# nadajnik.net
KiCad netlist of a schematic drawn in EAGLE
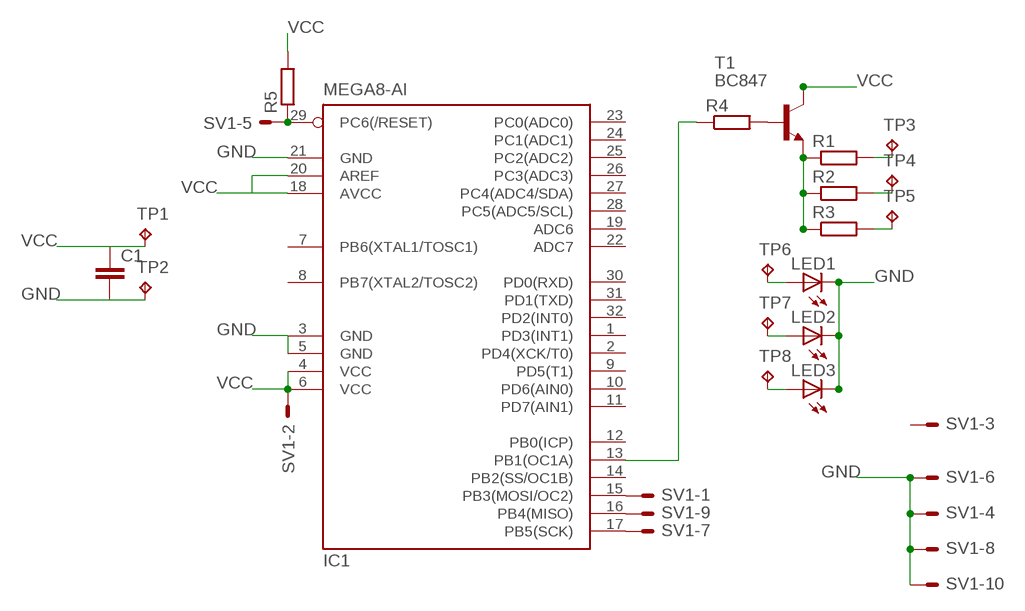
[diagram p0: schematic, sheet 1]

(export (version "E")
  (design (tool "Eeschema 10.0.6"))
  (components
    (comp (ref "C1")
      (value "C-EUC1206")
      (footprint "eagle-import:C1206")
      (libsource (lib "eagle-import") (part "C-EUC1206"))
    )
    (comp (ref "IC1")
      (value "MEGA8-AI")
      (footprint "eagle-import:TQFP32-08")
      (fields (field (name "MPN") "ATMEGA8-16AU"))
      (libsource (lib "eagle-import") (part "MEGA8-AI"))
    )
    (comp (ref "LED1")
      (value "LEDSFH480")
      (footprint "eagle-import:SFH480")
      (libsource (lib "eagle-import") (part "LEDSFH480"))
    )
    (comp (ref "LED2")
      (value "LEDSFH480")
      (footprint "eagle-import:SFH480")
      (libsource (lib "eagle-import") (part "LEDSFH480"))
    )
    (comp (ref "LED3")
      (value "LEDSFH480")
      (footprint "eagle-import:SFH480")
      (libsource (lib "eagle-import") (part "LEDSFH480"))
    )
    (comp (ref "R1")
      (value "R-EU_R1206")
      (footprint "eagle-import:R1206")
      (libsource (lib "eagle-import") (part "resistor_R-EU_R1206"))
    )
    (comp (ref "R2")
      (value "R-EU_R1206")
      (footprint "eagle-import:R1206")
      (libsource (lib "eagle-import") (part "resistor_R-EU_R1206"))
    )
    (comp (ref "R3")
      (value "R-EU_R1206")
      (footprint "eagle-import:R1206")
      (libsource (lib "eagle-import") (part "resistor_R-EU_R1206"))
    )
    (comp (ref "R4")
      (value "R-EU_R1206")
      (footprint "eagle-import:R1206")
      (libsource (lib "eagle-import") (part "R-EU_R1206"))
    )
    (comp (ref "R5")
      (value "R-EU_R1206")
      (footprint "eagle-import:R1206")
      (libsource (lib "eagle-import") (part "R-EU_R1206"))
    )
    (comp (ref "SV1")
      (value "ML10E")
      (footprint "eagle-import:ML10")
      (libsource (lib "eagle-import") (part "ML10E"))
    )
    (comp (ref "T1")
      (value "BC847")
      (footprint "eagle-import:SOT23")
      (libsource (lib "eagle-import") (part "BC847"))
    )
    (comp (ref "TP1")
      (value "TPPAD1-13Y")
      (footprint "eagle-import:P1-13Y")
      (libsource (lib "eagle-import") (part "TPPAD1-13Y"))
    )
    (comp (ref "TP2")
      (value "TPPAD1-13Y")
      (footprint "eagle-import:P1-13Y")
      (libsource (lib "eagle-import") (part "TPPAD1-13Y"))
    )
    (comp (ref "TP3")
      (value "TPPAD1-13Y")
      (footprint "eagle-import:P1-13Y")
      (libsource (lib "eagle-import") (part "TPPAD1-13Y"))
    )
    (comp (ref "TP4")
      (value "TPPAD1-13Y")
      (footprint "eagle-import:P1-13Y")
      (libsource (lib "eagle-import") (part "TPPAD1-13Y"))
    )
    (comp (ref "TP5")
      (value "TPPAD1-13Y")
      (footprint "eagle-import:P1-13Y")
      (libsource (lib "eagle-import") (part "TPPAD1-13Y"))
    )
    (comp (ref "TP6")
      (value "TPPAD1-13Y")
      (footprint "eagle-import:P1-13Y")
      (libsource (lib "eagle-import") (part "TPPAD1-13Y"))
    )
    (comp (ref "TP7")
      (value "TPPAD1-13Y")
      (footprint "eagle-import:P1-13Y")
      (libsource (lib "eagle-import") (part "TPPAD1-13Y"))
    )
    (comp (ref "TP8")
      (value "TPPAD1-13Y")
      (footprint "eagle-import:P1-13Y")
      (libsource (lib "eagle-import") (part "TPPAD1-13Y"))
    )
  )
  (nets
    (net (code "1") (name "/GND") (class "Default")
      (node (ref "C1") (pin "2") (pinfunction "2_2") (pintype "passive"))
      (node (ref "IC1") (pin "21") (pinfunction "GND_21") (pintype "power_in"))
      (node (ref "IC1") (pin "3") (pinfunction "GND_3") (pintype "power_in"))
      (node (ref "IC1") (pin "5") (pinfunction "GND_5") (pintype "power_in"))
      (node (ref "LED1") (pin "K") (pinfunction "C_K") (pintype "passive"))
      (node (ref "LED2") (pin "K") (pinfunction "C_K") (pintype "passive"))
      (node (ref "LED3") (pin "K") (pinfunction "C_K") (pintype "passive"))
      (node (ref "SV1") (pin "10") (pinfunction "S_10") (pintype "passive"))
      (node (ref "SV1") (pin "4") (pinfunction "S_4") (pintype "passive"))
      (node (ref "SV1") (pin "6") (pinfunction "S_6") (pintype "passive"))
      (node (ref "SV1") (pin "8") (pinfunction "S_8") (pintype "passive"))
      (node (ref "TP2") (pin "TP") (pinfunction "TP_TP") (pintype "input"))
    )
    (net (code "2") (name "/VCC") (class "Default")
      (node (ref "C1") (pin "1") (pinfunction "1_1") (pintype "passive"))
      (node (ref "IC1") (pin "18") (pinfunction "AVCC_18") (pintype "power_in"))
      (node (ref "IC1") (pin "20") (pinfunction "AREF_20") (pintype "passive"))
      (node (ref "IC1") (pin "4") (pinfunction "VCC_4") (pintype "power_in"))
      (node (ref "IC1") (pin "6") (pinfunction "VCC_6") (pintype "power_in"))
      (node (ref "R5") (pin "2") (pinfunction "2_2") (pintype "passive"))
      (node (ref "SV1") (pin "2") (pinfunction "S_2") (pintype "passive"))
      (node (ref "T1") (pin "3") (pinfunction "C_3") (pintype "passive"))
      (node (ref "TP1") (pin "TP") (pinfunction "TP_TP") (pintype "input"))
    )
    (net (code "3") (name "Net-(IC1-PB1(OC1A))") (class "Default")
      (node (ref "IC1") (pin "13") (pinfunction "PB1(OC1A)_13") (pintype "bidirectional"))
      (node (ref "R4") (pin "1") (pinfunction "1_1") (pintype "passive"))
    )
    (net (code "4") (name "Net-(IC1-PB3(MOSI{slash}OC2))") (class "Default")
      (node (ref "IC1") (pin "15") (pinfunction "PB3(MOSI/OC2)_15") (pintype "bidirectional"))
      (node (ref "SV1") (pin "1") (pinfunction "S_1") (pintype "passive"))
    )
    (net (code "5") (name "Net-(IC1-PB4(MISO))") (class "Default")
      (node (ref "IC1") (pin "16") (pinfunction "PB4(MISO)_16") (pintype "bidirectional"))
      (node (ref "SV1") (pin "9") (pinfunction "S_9") (pintype "passive"))
    )
    (net (code "6") (name "Net-(IC1-PB5(SCK))") (class "Default")
      (node (ref "IC1") (pin "17") (pinfunction "PB5(SCK)_17") (pintype "bidirectional"))
      (node (ref "SV1") (pin "7") (pinfunction "S_7") (pintype "passive"))
    )
    (net (code "7") (name "Net-(IC1-PC6({slash}RESET))") (class "Default")
      (node (ref "IC1") (pin "29") (pinfunction "PC6(/RESET)_29") (pintype "bidirectional"))
      (node (ref "R5") (pin "1") (pinfunction "1_1") (pintype "passive"))
      (node (ref "SV1") (pin "5") (pinfunction "S_5") (pintype "passive"))
    )
    (net (code "8") (name "Net-(LED1-PadA)") (class "Default")
      (node (ref "LED1") (pin "A") (pinfunction "A_A") (pintype "passive"))
      (node (ref "TP6") (pin "TP") (pinfunction "TP_TP") (pintype "input"))
    )
    (net (code "9") (name "Net-(LED2-PadA)") (class "Default")
      (node (ref "LED2") (pin "A") (pinfunction "A_A") (pintype "passive"))
      (node (ref "TP7") (pin "TP") (pinfunction "TP_TP") (pintype "input"))
    )
    (net (code "10") (name "Net-(LED3-PadA)") (class "Default")
      (node (ref "LED3") (pin "A") (pinfunction "A_A") (pintype "passive"))
      (node (ref "TP8") (pin "TP") (pinfunction "TP_TP") (pintype "input"))
    )
    (net (code "11") (name "Net-(R1-Pad2)") (class "Default")
      (node (ref "R1") (pin "2") (pinfunction "2_2") (pintype "passive"))
      (node (ref "TP3") (pin "TP") (pinfunction "TP_TP") (pintype "input"))
    )
    (net (code "12") (name "Net-(R2-Pad2)") (class "Default")
      (node (ref "R2") (pin "2") (pinfunction "2_2") (pintype "passive"))
      (node (ref "TP4") (pin "TP") (pinfunction "TP_TP") (pintype "input"))
    )
    (net (code "13") (name "Net-(R3-Pad2)") (class "Default")
      (node (ref "R3") (pin "2") (pinfunction "2_2") (pintype "passive"))
      (node (ref "TP5") (pin "TP") (pinfunction "TP_TP") (pintype "input"))
    )
    (net (code "14") (name "Net-(T1-B)") (class "Default")
      (node (ref "R4") (pin "2") (pinfunction "2_2") (pintype "passive"))
      (node (ref "T1") (pin "1") (pinfunction "B_1") (pintype "passive"))
    )
    (net (code "15") (name "Net-(T1-E)") (class "Default")
      (node (ref "R1") (pin "1") (pinfunction "1_1") (pintype "passive"))
      (node (ref "R2") (pin "1") (pinfunction "1_1") (pintype "passive"))
      (node (ref "R3") (pin "1") (pinfunction "1_1") (pintype "passive"))
      (node (ref "T1") (pin "2") (pinfunction "E_2") (pintype "passive"))
    )
    (net (code "16") (name "unconnected-(IC1-ADC6-Pad19)") (class "Default")
      (node (ref "IC1") (pin "19") (pinfunction "ADC6_19") (pintype "bidirectional"))
    )
    (net (code "17") (name "unconnected-(IC1-ADC7-Pad22)") (class "Default")
      (node (ref "IC1") (pin "22") (pinfunction "ADC7_22") (pintype "bidirectional"))
    )
    (net (code "18") (name "unconnected-(IC1-PB0(ICP)-Pad12)") (class "Default")
      (node (ref "IC1") (pin "12") (pinfunction "PB0(ICP)_12") (pintype "bidirectional"))
    )
    (net (code "19") (name "unconnected-(IC1-PB2(SS{slash}OC1B)-Pad14)") (class "Default")
      (node (ref "IC1") (pin "14") (pinfunction "PB2(SS/OC1B)_14") (pintype "bidirectional"))
    )
    (net (code "20") (name "unconnected-(IC1-PB6(XTAL1{slash}TOSC1)-Pad7)") (class "Default")
      (node (ref "IC1") (pin "7") (pinfunction "PB6(XTAL1/TOSC1)_7") (pintype "bidirectional"))
    )
    (net (code "21") (name "unconnected-(IC1-PB7(XTAL2{slash}TOSC2)-Pad8)") (class "Default")
      (node (ref "IC1") (pin "8") (pinfunction "PB7(XTAL2/TOSC2)_8") (pintype "bidirectional"))
    )
    (net (code "22") (name "unconnected-(IC1-PC0(ADC0)-Pad23)") (class "Default")
      (node (ref "IC1") (pin "23") (pinfunction "PC0(ADC0)_23") (pintype "bidirectional"))
    )
    (net (code "23") (name "unconnected-(IC1-PC1(ADC1)-Pad24)") (class "Default")
      (node (ref "IC1") (pin "24") (pinfunction "PC1(ADC1)_24") (pintype "bidirectional"))
    )
    (net (code "24") (name "unconnected-(IC1-PC2(ADC2)-Pad25)") (class "Default")
      (node (ref "IC1") (pin "25") (pinfunction "PC2(ADC2)_25") (pintype "bidirectional"))
    )
    (net (code "25") (name "unconnected-(IC1-PC3(ADC3)-Pad26)") (class "Default")
      (node (ref "IC1") (pin "26") (pinfunction "PC3(ADC3)_26") (pintype "bidirectional"))
    )
    (net (code "26") (name "unconnected-(IC1-PC4(ADC4{slash}SDA)-Pad27)") (class "Default")
      (node (ref "IC1") (pin "27") (pinfunction "PC4(ADC4/SDA)_27") (pintype "bidirectional"))
    )
    (net (code "27") (name "unconnected-(IC1-PC5(ADC5{slash}SCL)-Pad28)") (class "Default")
      (node (ref "IC1") (pin "28") (pinfunction "PC5(ADC5/SCL)_28") (pintype "bidirectional"))
    )
    (net (code "28") (name "unconnected-(IC1-PD0(RXD)-Pad30)") (class "Default")
      (node (ref "IC1") (pin "30") (pinfunction "PD0(RXD)_30") (pintype "bidirectional"))
    )
    (net (code "29") (name "unconnected-(IC1-PD1(TXD)-Pad31)") (class "Default")
      (node (ref "IC1") (pin "31") (pinfunction "PD1(TXD)_31") (pintype "bidirectional"))
    )
    (net (code "30") (name "unconnected-(IC1-PD2(INT0)-Pad32)") (class "Default")
      (node (ref "IC1") (pin "32") (pinfunction "PD2(INT0)_32") (pintype "bidirectional"))
    )
    (net (code "31") (name "unconnected-(IC1-PD3(INT1)-Pad1)") (class "Default")
      (node (ref "IC1") (pin "1") (pinfunction "PD3(INT1)_1") (pintype "bidirectional"))
    )
    (net (code "32") (name "unconnected-(IC1-PD4(XCK{slash}T0)-Pad2)") (class "Default")
      (node (ref "IC1") (pin "2") (pinfunction "PD4(XCK/T0)_2") (pintype "bidirectional"))
    )
    (net (code "33") (name "unconnected-(IC1-PD5(T1)-Pad9)") (class "Default")
      (node (ref "IC1") (pin "9") (pinfunction "PD5(T1)_9") (pintype "bidirectional"))
    )
    (net (code "34") (name "unconnected-(IC1-PD6(AIN0)-Pad10)") (class "Default")
      (node (ref "IC1") (pin "10") (pinfunction "PD6(AIN0)_10") (pintype "bidirectional"))
    )
    (net (code "35") (name "unconnected-(IC1-PD7(AIN1)-Pad11)") (class "Default")
      (node (ref "IC1") (pin "11") (pinfunction "PD7(AIN1)_11") (pintype "bidirectional"))
    )
    (net (code "36") (name "unconnected-(SV1D-S-Pad3)") (class "Default")
      (node (ref "SV1") (pin "3") (pinfunction "S_3") (pintype "passive"))
    )
  )
)
